# SparkFun-Blynk-Board-ESP8266.net
KiCad netlist of a schematic drawn in EAGLE
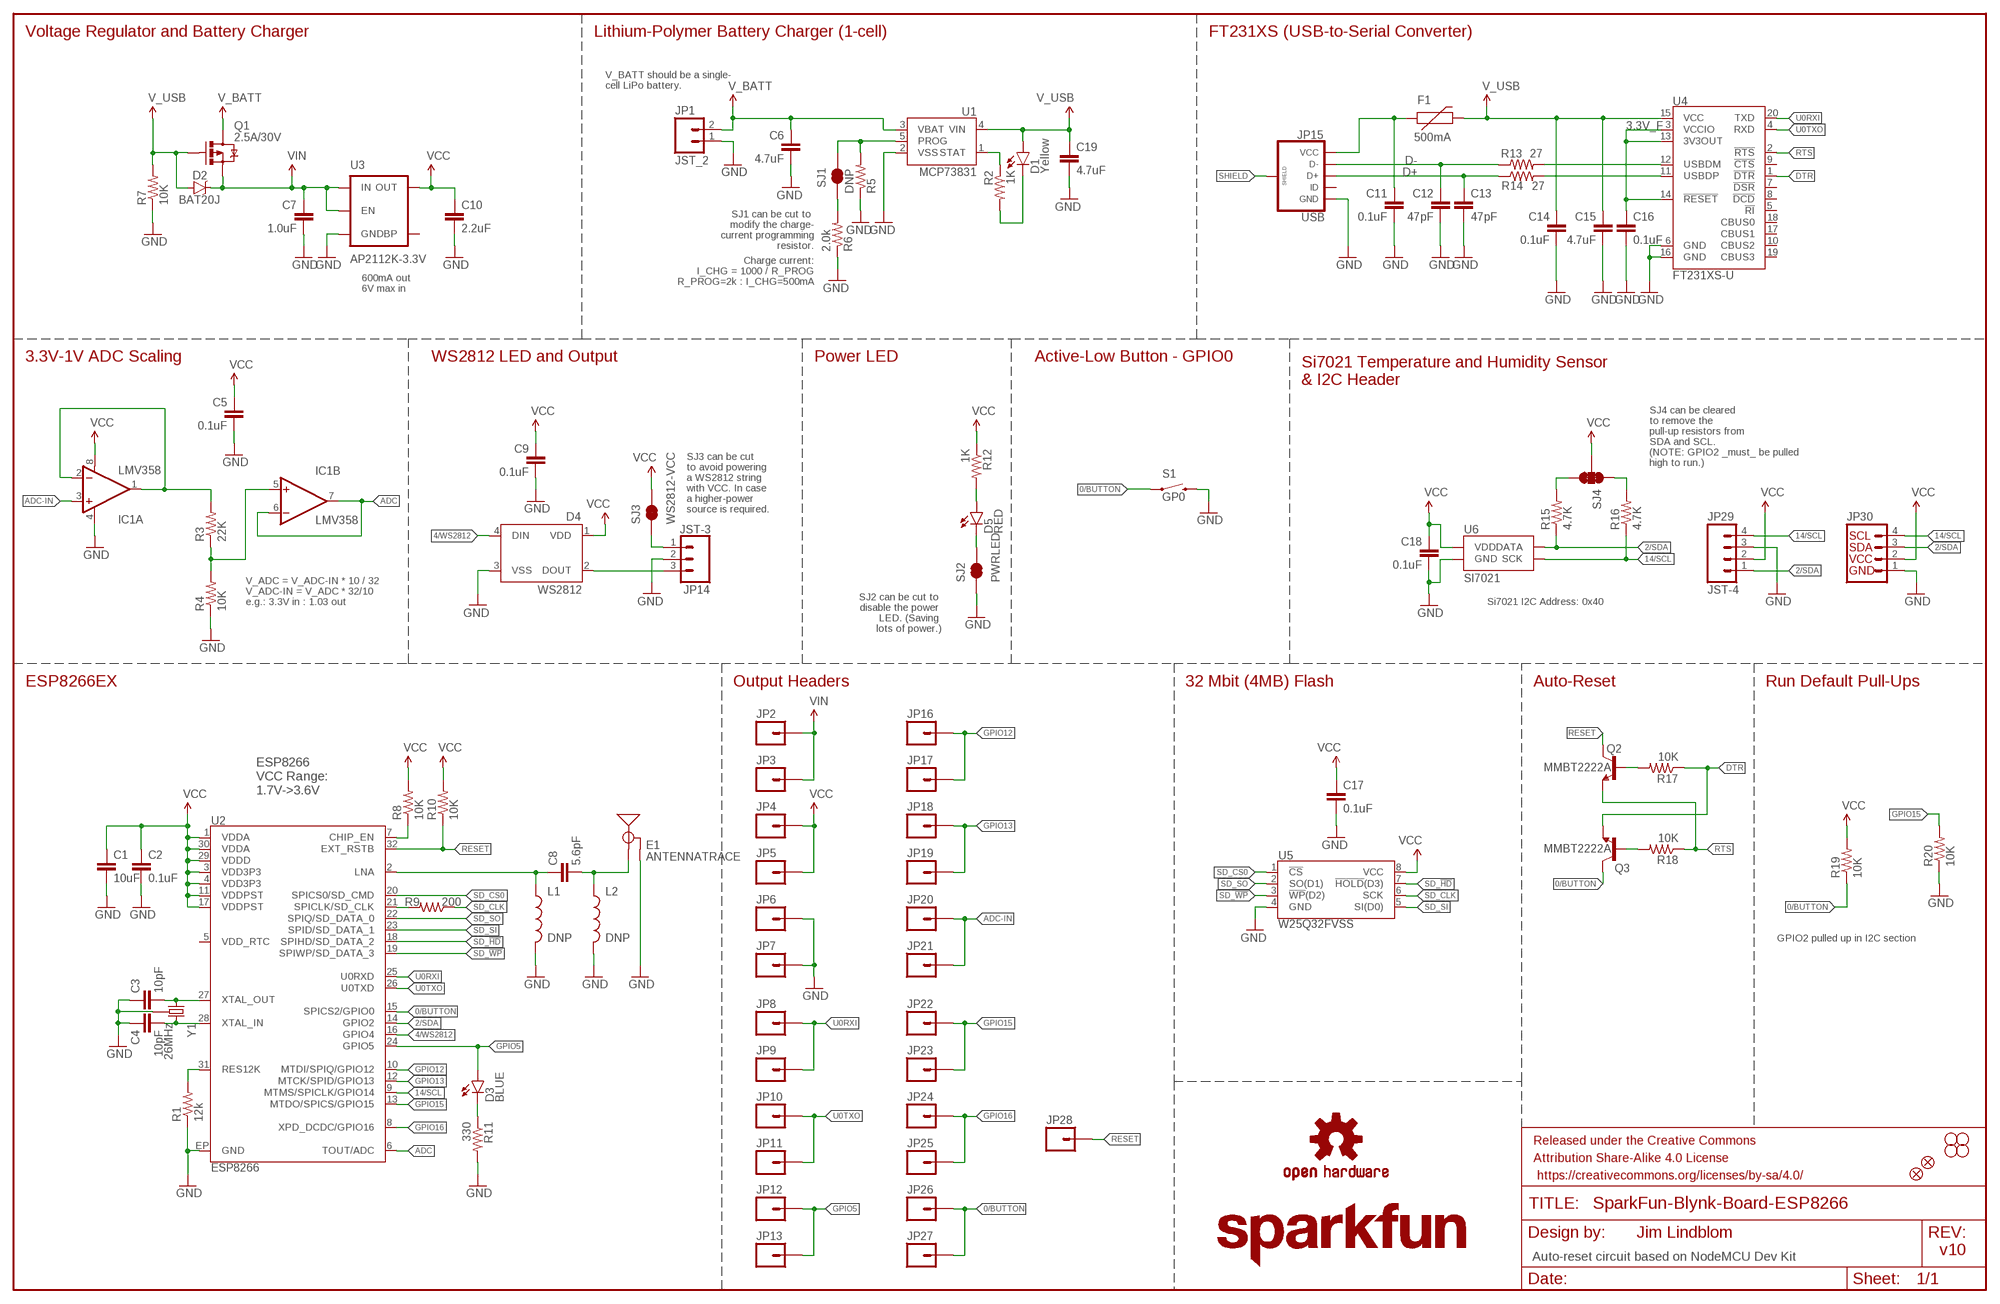
[diagram p0: schematic, sheet 1]

(export (version "E")
  (design (tool "Eeschema 10.0.6"))
  (components
    (comp (ref "C1")
      (value "10uF")
      (footprint "eagle-import:0603-CAP")
      (libsource (lib "eagle-import") (part "10UF-6.3V-20%(0603)"))
    )
    (comp (ref "C2")
      (value "0.1uF")
      (footprint "eagle-import:0603-CAP")
      (libsource (lib "eagle-import") (part "0.1UF-25V(+80/-20%)(0603)"))
    )
    (comp (ref "C3")
      (value "10pF")
      (footprint "eagle-import:0603-CAP")
      (libsource (lib "eagle-import") (part "10PF-50V-5%(0603)"))
    )
    (comp (ref "C4")
      (value "10pF")
      (footprint "eagle-import:0603-CAP")
      (libsource (lib "eagle-import") (part "10PF-50V-5%(0603)"))
    )
    (comp (ref "C5")
      (value "0.1uF")
      (footprint "eagle-import:0603-CAP")
      (libsource (lib "eagle-import") (part "0.1UF-25V(+80/-20%)(0603)"))
    )
    (comp (ref "C6")
      (value "4.7uF")
      (footprint "eagle-import:0603-CAP")
      (libsource (lib "eagle-import") (part "4.7UF-6.3V-10%(0603)0603"))
    )
    (comp (ref "C7")
      (value "1.0uF")
      (footprint "eagle-import:0805-CAP")
      (libsource (lib "eagle-import") (part "1.0UF-25V-+80/-20(0805){dblquote}"))
    )
    (comp (ref "C8")
      (value "5.6pF")
      (footprint "eagle-import:0603-CAP")
      (libsource (lib "eagle-import") (part "CAP0603-CAP"))
    )
    (comp (ref "C9")
      (value "0.1uF")
      (footprint "eagle-import:0603-CAP")
      (libsource (lib "eagle-import") (part "0.1UF-25V(+80/-20%)(0603)"))
    )
    (comp (ref "C10")
      (value "2.2uF")
      (footprint "eagle-import:0603-CAP")
      (libsource (lib "eagle-import") (part "2.2UF-10V-20%(0603)"))
    )
    (comp (ref "C11")
      (value "0.1uF")
      (footprint "eagle-import:0603-CAP")
      (libsource (lib "eagle-import") (part "0.1UF-25V(+80/-20%)(0603)"))
    )
    (comp (ref "C12")
      (value "47pF")
      (footprint "eagle-import:0603-CAP")
      (libsource (lib "eagle-import") (part "47PF-50V-5%(0603)"))
    )
    (comp (ref "C13")
      (value "47pF")
      (footprint "eagle-import:0603-CAP")
      (libsource (lib "eagle-import") (part "47PF-50V-5%(0603)"))
    )
    (comp (ref "C14")
      (value "0.1uF")
      (footprint "eagle-import:0603-CAP")
      (libsource (lib "eagle-import") (part "0.1UF-25V(+80/-20%)(0603)"))
    )
    (comp (ref "C15")
      (value "4.7uF")
      (footprint "eagle-import:0603-CAP")
      (libsource (lib "eagle-import") (part "4.7UF-6.3V-10%(0603)0603"))
    )
    (comp (ref "C16")
      (value "0.1uF")
      (footprint "eagle-import:0603-CAP")
      (libsource (lib "eagle-import") (part "0.1UF-25V(+80/-20%)(0603)"))
    )
    (comp (ref "C17")
      (value "0.1uF")
      (footprint "eagle-import:0603-CAP")
      (libsource (lib "eagle-import") (part "0.1UF-25V(+80/-20%)(0603)"))
    )
    (comp (ref "C18")
      (value "0.1uF")
      (footprint "eagle-import:0603-CAP")
      (libsource (lib "eagle-import") (part "0.1UF-25V(+80/-20%)(0603)"))
    )
    (comp (ref "C19")
      (value "4.7uF")
      (footprint "eagle-import:0603-CAP")
      (libsource (lib "eagle-import") (part "4.7UF-6.3V-10%(0603)0603"))
    )
    (comp (ref "D1")
      (value "Yellow")
      (footprint "eagle-import:LED-0603")
      (libsource (lib "eagle-import") (part "LED-YELLOW0603"))
    )
    (comp (ref "D2")
      (value "BAT20J")
      (footprint "eagle-import:SOD-323")
      (libsource (lib "eagle-import") (part "DIODE-SCHOTTKY-BAT20J"))
    )
    (comp (ref "D3")
      (value "BLUE")
      (footprint "eagle-import:LED-0603")
      (libsource (lib "eagle-import") (part "LED-BLUE0603"))
    )
    (comp (ref "D4")
      (value "WS2812")
      (footprint "eagle-import:WS2812B")
      (libsource (lib "eagle-import") (part "WS2812B"))
    )
    (comp (ref "D5")
      (value "RED")
      (footprint "eagle-import:LED-0603")
      (libsource (lib "eagle-import") (part "LED-RED0603"))
    )
    (comp (ref "E1")
      (value "ANTENNATRACE")
      (footprint "eagle-import:TRACE_ANTENNA_2.4GHZ_25.7MM")
      (libsource (lib "eagle-import") (part "ANTENNATRACE"))
    )
    (comp (ref "F1")
      (value "500mA")
      (footprint "eagle-import:PTC-1206")
      (libsource (lib "eagle-import") (part "PTCSMD"))
    )
    (comp (ref "FID1")
      (value "FIDUCIAL1X2")
      (footprint "eagle-import:FIDUCIAL-1X2")
      (libsource (lib "eagle-import") (part "FIDUCIAL1X2"))
    )
    (comp (ref "FID2")
      (value "FIDUCIAL1X2")
      (footprint "eagle-import:FIDUCIAL-1X2")
      (libsource (lib "eagle-import") (part "FIDUCIAL1X2"))
    )
    (comp (ref "FRAME1")
      (value "FRAME-LEDGER")
      (footprint "eagle-import:CREATIVE_COMMONS")
      (libsource (lib "eagle-import") (part "FRAME-LEDGER"))
    )
    (comp (ref "IC1")
      (value "LMV358")
      (footprint "eagle-import:SO08")
      (fields (field (name "PROD_ID") "IC-09657"))
      (libsource (lib "eagle-import") (part "OPAMP-DUALU"))
    )
    (comp (ref "JP1")
      (value "JST_2")
      (footprint "eagle-import:JST-2-PTH")
      (libsource (lib "eagle-import") (part "M02JST-PTH-2"))
    )
    (comp (ref "JP2")
      (value "DNP")
      (footprint "eagle-import:1X01_ALLIGATOR_3MM_HALF")
      (libsource (lib "eagle-import") (part "M01ALLIGATOR_HALF"))
    )
    (comp (ref "JP3")
      (value "DNP")
      (footprint "eagle-import:1X01_NO_SILK")
      (libsource (lib "eagle-import") (part "M01PTH_NO_SILK_YES_STOP"))
    )
    (comp (ref "JP4")
      (value "DNP")
      (footprint "eagle-import:1X01_ALLIGATOR_3MM_HALF")
      (libsource (lib "eagle-import") (part "M01ALLIGATOR_HALF"))
    )
    (comp (ref "JP5")
      (value "DNP")
      (footprint "eagle-import:1X01_NO_SILK")
      (libsource (lib "eagle-import") (part "M01PTH_NO_SILK_YES_STOP"))
    )
    (comp (ref "JP6")
      (value "DNP")
      (footprint "eagle-import:1X01_ALLIGATOR_3MM_HALF")
      (libsource (lib "eagle-import") (part "M01ALLIGATOR_HALF"))
    )
    (comp (ref "JP7")
      (value "DNP")
      (footprint "eagle-import:1X01_NO_SILK")
      (libsource (lib "eagle-import") (part "M01PTH_NO_SILK_YES_STOP"))
    )
    (comp (ref "JP8")
      (value "DNP")
      (footprint "eagle-import:1X01_ALLIGATOR_3MM_HALF")
      (libsource (lib "eagle-import") (part "M01ALLIGATOR_HALF"))
    )
    (comp (ref "JP9")
      (value "DNP")
      (footprint "eagle-import:1X01_NO_SILK")
      (libsource (lib "eagle-import") (part "M01PTH_NO_SILK_YES_STOP"))
    )
    (comp (ref "JP10")
      (value "DNP")
      (footprint "eagle-import:1X01_ALLIGATOR_3MM_HALF")
      (libsource (lib "eagle-import") (part "M01ALLIGATOR_HALF"))
    )
    (comp (ref "JP11")
      (value "DNP")
      (footprint "eagle-import:1X01_NO_SILK")
      (libsource (lib "eagle-import") (part "M01PTH_NO_SILK_YES_STOP"))
    )
    (comp (ref "JP12")
      (value "DNP")
      (footprint "eagle-import:1X01_ALLIGATOR_3MM_HALF")
      (libsource (lib "eagle-import") (part "M01ALLIGATOR_HALF"))
    )
    (comp (ref "JP13")
      (value "DNP")
      (footprint "eagle-import:1X01_NO_SILK")
      (libsource (lib "eagle-import") (part "M01PTH_NO_SILK_YES_STOP"))
    )
    (comp (ref "JP14")
      (value "JST-3")
      (footprint "eagle-import:JST-3-PTH-VERT")
      (libsource (lib "eagle-import") (part "M03JST-PTH-VERT"))
    )
    (comp (ref "JP15")
      (value "USB")
      (footprint "eagle-import:USB-B-MICRO-SMD_V03")
      (libsource (lib "eagle-import") (part "USB_MICROB_PLUGCONN-11752"))
    )
    (comp (ref "JP16")
      (value "DNP")
      (footprint "eagle-import:1X01_ALLIGATOR_3MM_HALF")
      (libsource (lib "eagle-import") (part "M01ALLIGATOR_HALF"))
    )
    (comp (ref "JP17")
      (value "DNP")
      (footprint "eagle-import:1X01_NO_SILK")
      (libsource (lib "eagle-import") (part "M01PTH_NO_SILK_YES_STOP"))
    )
    (comp (ref "JP18")
      (value "DNP")
      (footprint "eagle-import:1X01_ALLIGATOR_3MM_HALF")
      (libsource (lib "eagle-import") (part "M01ALLIGATOR_HALF"))
    )
    (comp (ref "JP19")
      (value "DNP")
      (footprint "eagle-import:1X01_NO_SILK")
      (libsource (lib "eagle-import") (part "M01PTH_NO_SILK_YES_STOP"))
    )
    (comp (ref "JP20")
      (value "DNP")
      (footprint "eagle-import:1X01_ALLIGATOR_3MM_HALF")
      (libsource (lib "eagle-import") (part "M01ALLIGATOR_HALF"))
    )
    (comp (ref "JP21")
      (value "DNP")
      (footprint "eagle-import:1X01_NO_SILK")
      (libsource (lib "eagle-import") (part "M01PTH_NO_SILK_YES_STOP"))
    )
    (comp (ref "JP22")
      (value "DNP")
      (footprint "eagle-import:1X01_ALLIGATOR_3MM_HALF")
      (libsource (lib "eagle-import") (part "M01ALLIGATOR_HALF"))
    )
    (comp (ref "JP23")
      (value "DNP")
      (footprint "eagle-import:1X01_NO_SILK")
      (libsource (lib "eagle-import") (part "M01PTH_NO_SILK_YES_STOP"))
    )
    (comp (ref "JP24")
      (value "DNP")
      (footprint "eagle-import:1X01_ALLIGATOR_3MM_HALF")
      (libsource (lib "eagle-import") (part "M01ALLIGATOR_HALF"))
    )
    (comp (ref "JP25")
      (value "DNP")
      (footprint "eagle-import:1X01_NO_SILK")
      (libsource (lib "eagle-import") (part "M01PTH_NO_SILK_YES_STOP"))
    )
    (comp (ref "JP26")
      (value "DNP")
      (footprint "eagle-import:1X01_ALLIGATOR_3MM_HALF")
      (libsource (lib "eagle-import") (part "M01ALLIGATOR_HALF"))
    )
    (comp (ref "JP27")
      (value "DNP")
      (footprint "eagle-import:1X01_NO_SILK")
      (libsource (lib "eagle-import") (part "M01PTH_NO_SILK_YES_STOP"))
    )
    (comp (ref "JP28")
      (value "DNP")
      (footprint "eagle-import:1X01_NO_SILK")
      (libsource (lib "eagle-import") (part "M01PTH_NO_SILK_YES_STOP"))
    )
    (comp (ref "JP29")
      (value "JST-4")
      (footprint "eagle-import:JST-4-PTH-VERT")
      (libsource (lib "eagle-import") (part "M04JST-PTH-VERT"))
    )
    (comp (ref "JP30")
      (value "DNP")
      (footprint "eagle-import:1X04_NO_SILK")
      (libsource (lib "eagle-import") (part "I2C_STANDARD_NO_SILK"))
    )
    (comp (ref "L1")
      (value "DNP")
      (footprint "eagle-import:0603")
      (libsource (lib "eagle-import") (part "INDUCTOR0603"))
    )
    (comp (ref "L2")
      (value "DNP")
      (footprint "eagle-import:0603")
      (libsource (lib "eagle-import") (part "INDUCTOR0603"))
    )
    (comp (ref "LOGO1")
      (value "SFE_LOGO_NAME.2_INCH")
      (footprint "eagle-import:SFE_LOGO_NAME_.2")
      (libsource (lib "eagle-import") (part "SFE_LOGO_NAME.2_INCH"))
    )
    (comp (ref "LOGO2")
      (value "OSHW-LOGOS")
      (footprint "eagle-import:OSHW-LOGO-S")
      (libsource (lib "eagle-import") (part "OSHW-LOGOS"))
    )
    (comp (ref "LOGO3")
      (value "SFE_LOGO_NAME.3_INCH")
      (footprint "eagle-import:SFE_LOGO_NAME_.3")
      (libsource (lib "eagle-import") (part "SFE_LOGO_NAME.3_INCH"))
    )
    (comp (ref "Q1")
      (value "2.5A/30V")
      (footprint "eagle-import:SOT23-3")
      (libsource (lib "eagle-import") (part "MOSFET-PCHANNELDMG2307L"))
    )
    (comp (ref "Q2")
      (value "MMBT2222A")
      (footprint "eagle-import:SOT23-3@1")
      (libsource (lib "eagle-import") (part "TRANSISTOR_NPNMMBT2222A"))
    )
    (comp (ref "Q3")
      (value "MMBT2222A")
      (footprint "eagle-import:SOT23-3@1")
      (libsource (lib "eagle-import") (part "TRANSISTOR_NPNMMBT2222A"))
    )
    (comp (ref "R1")
      (value "12k")
      (footprint "eagle-import:0603-RES")
      (libsource (lib "eagle-import") (part "12KOHM-1/10W-1%(0603)"))
    )
    (comp (ref "R2")
      (value "1K")
      (footprint "eagle-import:0603-RES")
      (libsource (lib "eagle-import") (part "1KOHM-1/10W-1%(0603)"))
    )
    (comp (ref "R3")
      (value "22K")
      (footprint "eagle-import:0603-RES")
      (libsource (lib "eagle-import") (part "22KOHM1/10W1%(0603)"))
    )
    (comp (ref "R4")
      (value "10K")
      (footprint "eagle-import:0603-RES")
      (libsource (lib "eagle-import") (part "10KOHM-1/10W-1%(0603)0603"))
    )
    (comp (ref "R5")
      (value "DNP")
      (footprint "eagle-import:1_6W-RES")
      (libsource (lib "eagle-import") (part "RESISTORPTH-1/6W"))
    )
    (comp (ref "R6")
      (value "2.0k")
      (footprint "eagle-import:0603-RES")
      (libsource (lib "eagle-import") (part "2.0KOHM1/10W5%(0603)"))
    )
    (comp (ref "R7")
      (value "10K")
      (footprint "eagle-import:0603-RES@1")
      (libsource (lib "eagle-import") (part "10KOHM1/10W1%(0603)0603"))
    )
    (comp (ref "R8")
      (value "10K")
      (footprint "eagle-import:0603-RES@1")
      (libsource (lib "eagle-import") (part "10KOHM1/10W1%(0603)0603"))
    )
    (comp (ref "R9")
      (value "200")
      (footprint "eagle-import:0603-RES")
      (libsource (lib "eagle-import") (part "200OHM1/10W1%(0603)"))
    )
    (comp (ref "R10")
      (value "10K")
      (footprint "eagle-import:0603-RES@1")
      (libsource (lib "eagle-import") (part "10KOHM1/10W1%(0603)0603"))
    )
    (comp (ref "R11")
      (value "330")
      (footprint "eagle-import:0603-RES")
      (libsource (lib "eagle-import") (part "330OHM1/10W1%(0603)"))
    )
    (comp (ref "R12")
      (value "1K")
      (footprint "eagle-import:0603-RES")
      (libsource (lib "eagle-import") (part "1KOHM-1/10W-1%(0603)"))
    )
    (comp (ref "R13")
      (value "27")
      (footprint "eagle-import:0603-RES")
      (libsource (lib "eagle-import") (part "27OHM1/10W1%(0603)0603-RES"))
    )
    (comp (ref "R14")
      (value "27")
      (footprint "eagle-import:0603-RES")
      (libsource (lib "eagle-import") (part "27OHM1/10W1%(0603)0603-RES"))
    )
    (comp (ref "R15")
      (value "4.7K")
      (footprint "eagle-import:0603-RES")
      (libsource (lib "eagle-import") (part "4.7KOHM-1/10W-1%(0603)"))
    )
    (comp (ref "R16")
      (value "4.7K")
      (footprint "eagle-import:0603-RES")
      (libsource (lib "eagle-import") (part "4.7KOHM-1/10W-1%(0603)"))
    )
    (comp (ref "R17")
      (value "10K")
      (footprint "eagle-import:0603-RES@1")
      (libsource (lib "eagle-import") (part "10KOHM1/10W1%(0603)0603"))
    )
    (comp (ref "R18")
      (value "10K")
      (footprint "eagle-import:0603-RES@1")
      (libsource (lib "eagle-import") (part "10KOHM1/10W1%(0603)0603"))
    )
    (comp (ref "R19")
      (value "10K")
      (footprint "eagle-import:0603-RES@1")
      (libsource (lib "eagle-import") (part "10KOHM1/10W1%(0603)0603"))
    )
    (comp (ref "R20")
      (value "10K")
      (footprint "eagle-import:0603-RES@1")
      (libsource (lib "eagle-import") (part "10KOHM1/10W1%(0603)0603"))
    )
    (comp (ref "S1")
      (value "GP0")
      (footprint "eagle-import:TACTILE-SWITCH-SMD")
      (libsource (lib "eagle-import") (part "SWITCH-MOMENTARY-2SMD-REDUNDANT"))
    )
    (comp (ref "SJ1")
      (value "DNP")
      (footprint "eagle-import:PAD-JUMPER-2-NC_BY_TRACE_YES_SILK")
      (libsource (lib "eagle-import") (part "JUMPER-PAD-2-NC_BY_TRACE"))
    )
    (comp (ref "SJ2")
      (value "PWRLED")
      (footprint "eagle-import:PAD-JUMPER-2-NC_BY_TRACE_YES_SILK")
      (libsource (lib "eagle-import") (part "JUMPER-PAD-2-NC_BY_TRACE"))
    )
    (comp (ref "SJ3")
      (value "WS2812-VCC")
      (footprint "eagle-import:PAD-JUMPER-2-NC_BY_TRACE_YES_SILK")
      (libsource (lib "eagle-import") (part "JUMPER-PAD-2-NC_BY_TRACE"))
    )
    (comp (ref "SJ4")
      (value "DNP")
      (footprint "eagle-import:PAD-JUMPER-3-3OF3_NC_BY_TRACE_YES_SILK_FULL_BOX")
      (libsource (lib "eagle-import") (part "JUMPER-PAD-3-NC_BY_TRACE"))
    )
    (comp (ref "STANDOFF1")
      (value "STAND-OFF")
      (footprint "eagle-import:STAND-OFF")
      (libsource (lib "eagle-import") (part "STAND-OFF"))
    )
    (comp (ref "STANDOFF2")
      (value "STAND-OFF")
      (footprint "eagle-import:STAND-OFF")
      (libsource (lib "eagle-import") (part "STAND-OFF"))
    )
    (comp (ref "STANDOFF3")
      (value "STAND-OFF")
      (footprint "eagle-import:STAND-OFF")
      (libsource (lib "eagle-import") (part "STAND-OFF"))
    )
    (comp (ref "STANDOFF4")
      (value "STAND-OFF")
      (footprint "eagle-import:STAND-OFF")
      (libsource (lib "eagle-import") (part "STAND-OFF"))
    )
    (comp (ref "U1")
      (value "MCP73831")
      (footprint "eagle-import:SOT23-5")
      (libsource (lib "eagle-import") (part "MCP73831"))
    )
    (comp (ref "U2")
      (value "ESP8266")
      (footprint "eagle-import:QFN32")
      (fields (field (name "PROD_ID") "IC-12452"))
      (libsource (lib "eagle-import") (part "ESP8266"))
    )
    (comp (ref "U3")
      (value "AP2112K-3.3V")
      (footprint "eagle-import:SOT23-5")
      (libsource (lib "eagle-import") (part "V_REG_LDOSMD"))
    )
    (comp (ref "U4")
      (value "FT231XS-U")
      (footprint "eagle-import:SSOP20_L")
      (libsource (lib "eagle-import") (part "FT231XS"))
    )
    (comp (ref "U5")
      (value "W25Q32FVSS")
      (footprint "eagle-import:SOIC-8")
      (fields (field (name "PROD_ID") "IC-13229"))
      (libsource (lib "eagle-import") (part "W25Q32FVSS"))
    )
    (comp (ref "U6")
      (value "SI7021")
      (footprint "eagle-import:SI7021")
      (libsource (lib "eagle-import") (part "SI7021"))
    )
    (comp (ref "Y1")
      (value "26MHz")
      (footprint "eagle-import:CRYSTAL-SMD-3.2X2.5")
      (libsource (lib "eagle-import") (part "CRYSTAL-GROUNDED3.2X2.5"))
    )
  )
  (nets
    (net (code "1") (name "/3.3V_F") (class "Default")
      (node (ref "C16") (pin "1") (pinfunction "1_1") (pintype "passive"))
      (node (ref "U4") (pin "13") (pinfunction "3V3OUT_13") (pintype "bidirectional"))
      (node (ref "U4") (pin "14") (pinfunction "~{RESET}_14") (pintype "bidirectional"))
      (node (ref "U4") (pin "3") (pinfunction "VCCIO_3") (pintype "bidirectional"))
    )
    (net (code "2") (name "/D+") (class "Default")
      (node (ref "C13") (pin "1") (pinfunction "1_1") (pintype "passive"))
      (node (ref "JP15") (pin "D+") (pinfunction "D+_D+") (pintype "bidirectional"))
      (node (ref "R14") (pin "1") (pinfunction "1_1") (pintype "passive"))
    )
    (net (code "3") (name "/D-") (class "Default")
      (node (ref "C12") (pin "1") (pinfunction "1_1") (pintype "passive"))
      (node (ref "JP15") (pin "D-") (pinfunction "D-_D-") (pintype "bidirectional"))
      (node (ref "R13") (pin "1") (pinfunction "1_1") (pintype "passive"))
    )
    (net (code "4") (name "/SD_~{HD}") (class "Default")
      (node (ref "U2") (pin "18") (pinfunction "SPIHD/SD_DATA_2_18") (pintype "bidirectional"))
      (node (ref "U5") (pin "7") (pinfunction "~{HOLD}(D3)_7") (pintype "bidirectional"))
    )
    (net (code "5") (name "/SD_~{WP}") (class "Default")
      (node (ref "U2") (pin "19") (pinfunction "SPIWP/SD_DATA_3_19") (pintype "bidirectional"))
      (node (ref "U5") (pin "3") (pinfunction "~{WP}(D2)_3") (pintype "bidirectional"))
    )
    (net (code "6") (name "0{slash}BUTTON") (class "Default")
      (node (ref "JP26") (pin "1@2") (pinfunction "1_1@2") (pintype "passive"))
      (node (ref "JP27") (pin "1") (pinfunction "1_1") (pintype "passive"))
      (node (ref "Q3") (pin "3") (pinfunction "C_3") (pintype "passive"))
      (node (ref "R19") (pin "1") (pinfunction "1_1") (pintype "passive"))
      (node (ref "S1") (pin "1") (pinfunction "1_1") (pintype "passive"))
      (node (ref "S1") (pin "2") (pinfunction "1_2") (pintype "passive"))
      (node (ref "U2") (pin "15") (pinfunction "SPICS2/GPIO0_15") (pintype "bidirectional"))
    )
    (net (code "7") (name "2{slash}SDA") (class "Default")
      (node (ref "JP29") (pin "1") (pinfunction "1_1") (pintype "passive"))
      (node (ref "JP30") (pin "3") (pinfunction "3_3") (pintype "passive"))
      (node (ref "R15") (pin "1") (pinfunction "1_1") (pintype "passive"))
      (node (ref "U2") (pin "14") (pinfunction "GPIO2_14") (pintype "bidirectional"))
      (node (ref "U6") (pin "DATA") (pinfunction "DATA_DATA") (pintype "bidirectional"))
    )
    (net (code "8") (name "4{slash}WS2812") (class "Default")
      (node (ref "D4") (pin "4") (pinfunction "DIN_4") (pintype "input"))
      (node (ref "U2") (pin "16") (pinfunction "GPIO4_16") (pintype "bidirectional"))
    )
    (net (code "9") (name "14{slash}SCL") (class "Default")
      (node (ref "JP29") (pin "4") (pinfunction "4_4") (pintype "passive"))
      (node (ref "JP30") (pin "4") (pinfunction "4_4") (pintype "passive"))
      (node (ref "R16") (pin "1") (pinfunction "1_1") (pintype "passive"))
      (node (ref "U2") (pin "9") (pinfunction "MTMS/SPICLK/GPIO14_9") (pintype "bidirectional"))
      (node (ref "U6") (pin "SCK") (pinfunction "SCK_SCK") (pintype "input"))
    )
    (net (code "10") (name "ADC") (class "Default")
      (node (ref "IC1") (pin "6") (pinfunction "-IN_6") (pintype "input"))
      (node (ref "IC1") (pin "7") (pinfunction "OUT_7") (pintype "output"))
      (node (ref "U2") (pin "6") (pinfunction "TOUT/ADC_6") (pintype "bidirectional"))
    )
    (net (code "11") (name "ADC-IN") (class "Default")
      (node (ref "IC1") (pin "3") (pinfunction "+IN_3") (pintype "input"))
      (node (ref "JP20") (pin "1@2") (pinfunction "1_1@2") (pintype "passive"))
      (node (ref "JP21") (pin "1") (pinfunction "1_1") (pintype "passive"))
    )
    (net (code "12") (name "DTR") (class "Default")
      (node (ref "Q3") (pin "2") (pinfunction "E_2") (pintype "passive"))
      (node (ref "R17") (pin "1") (pinfunction "1_1") (pintype "passive"))
      (node (ref "U4") (pin "1") (pinfunction "~{DTR}_1") (pintype "bidirectional"))
    )
    (net (code "13") (name "GND") (class "Default")
      (node (ref "C1") (pin "2") (pinfunction "2_2") (pintype "passive"))
      (node (ref "C10") (pin "2") (pinfunction "2_2") (pintype "passive"))
      (node (ref "C11") (pin "2") (pinfunction "2_2") (pintype "passive"))
      (node (ref "C12") (pin "2") (pinfunction "2_2") (pintype "passive"))
      (node (ref "C13") (pin "2") (pinfunction "2_2") (pintype "passive"))
      (node (ref "C14") (pin "2") (pinfunction "2_2") (pintype "passive"))
      (node (ref "C15") (pin "2") (pinfunction "2_2") (pintype "passive"))
      (node (ref "C16") (pin "2") (pinfunction "2_2") (pintype "passive"))
      (node (ref "C17") (pin "2") (pinfunction "2_2") (pintype "passive"))
      (node (ref "C18") (pin "2") (pinfunction "2_2") (pintype "passive"))
      (node (ref "C19") (pin "2") (pinfunction "2_2") (pintype "passive"))
      (node (ref "C2") (pin "2") (pinfunction "2_2") (pintype "passive"))
      (node (ref "C3") (pin "1") (pinfunction "1_1") (pintype "passive"))
      (node (ref "C4") (pin "1") (pinfunction "1_1") (pintype "passive"))
      (node (ref "C5") (pin "2") (pinfunction "2_2") (pintype "passive"))
      (node (ref "C6") (pin "2") (pinfunction "2_2") (pintype "passive"))
      (node (ref "C7") (pin "2") (pinfunction "2_2") (pintype "passive"))
      (node (ref "C9") (pin "2") (pinfunction "2_2") (pintype "passive"))
      (node (ref "D4") (pin "3") (pinfunction "VSS_3") (pintype "power_in"))
      (node (ref "E1") (pin "GND") (pinfunction "GND_GND") (pintype "bidirectional"))
      (node (ref "E1") (pin "GND2") (pinfunction "GND_GND2") (pintype "bidirectional"))
      (node (ref "IC1") (pin "4") (pinfunction "V-_4") (pintype "power_in"))
      (node (ref "JP1") (pin "1") (pinfunction "1_1") (pintype "passive"))
      (node (ref "JP14") (pin "2") (pinfunction "2_2") (pintype "passive"))
      (node (ref "JP15") (pin "GND") (pinfunction "GND_GND") (pintype "bidirectional"))
      (node (ref "JP29") (pin "3") (pinfunction "3_3") (pintype "passive"))
      (node (ref "JP30") (pin "1") (pinfunction "1_1") (pintype "passive"))
      (node (ref "JP6") (pin "1@2") (pinfunction "1_1@2") (pintype "passive"))
      (node (ref "JP7") (pin "1") (pinfunction "1_1") (pintype "passive"))
      (node (ref "L1") (pin "2") (pinfunction "2_2") (pintype "passive"))
      (node (ref "L2") (pin "2") (pinfunction "2_2") (pintype "passive"))
      (node (ref "R1") (pin "1") (pinfunction "1_1") (pintype "passive"))
      (node (ref "R11") (pin "2") (pinfunction "2_2") (pintype "passive"))
      (node (ref "R20") (pin "1") (pinfunction "1_1") (pintype "passive"))
      (node (ref "R4") (pin "1") (pinfunction "1_1") (pintype "passive"))
      (node (ref "R5") (pin "1") (pinfunction "1_1") (pintype "passive"))
      (node (ref "R6") (pin "1") (pinfunction "1_1") (pintype "passive"))
      (node (ref "R7") (pin "1") (pinfunction "1_1") (pintype "passive"))
      (node (ref "S1") (pin "3") (pinfunction "2_3") (pintype "passive"))
      (node (ref "S1") (pin "4") (pinfunction "2_4") (pintype "passive"))
      (node (ref "SJ2") (pin "1") (pinfunction "1_1") (pintype "passive"))
      (node (ref "U1") (pin "2") (pinfunction "VSS_2") (pintype "power_in"))
      (node (ref "U2") (pin "EP") (pinfunction "GND_EP") (pintype "bidirectional"))
      (node (ref "U3") (pin "2") (pinfunction "GND_2") (pintype "input"))
      (node (ref "U4") (pin "16") (pinfunction "GND_16") (pintype "bidirectional"))
      (node (ref "U4") (pin "6") (pinfunction "GND_6") (pintype "bidirectional"))
      (node (ref "U5") (pin "4") (pinfunction "GND_4") (pintype "bidirectional"))
      (node (ref "U6") (pin "GND") (pinfunction "GND_GND") (pintype "power_in"))
      (node (ref "Y1") (pin "2") (pinfunction "GND_2") (pintype "passive"))
      (node (ref "Y1") (pin "4") (pinfunction "GND_4") (pintype "passive"))
    )
    (net (code "14") (name "GPIO5") (class "Default")
      (node (ref "D3") (pin "A") (pinfunction "A_A") (pintype "passive"))
      (node (ref "JP12") (pin "1@2") (pinfunction "1_1@2") (pintype "passive"))
      (node (ref "JP13") (pin "1") (pinfunction "1_1") (pintype "passive"))
      (node (ref "U2") (pin "24") (pinfunction "GPIO5_24") (pintype "bidirectional"))
    )
    (net (code "15") (name "GPIO12") (class "Default")
      (node (ref "JP16") (pin "1@2") (pinfunction "1_1@2") (pintype "passive"))
      (node (ref "JP17") (pin "1") (pinfunction "1_1") (pintype "passive"))
      (node (ref "U2") (pin "10") (pinfunction "MTDI/SPIQ/GPIO12_10") (pintype "bidirectional"))
    )
    (net (code "16") (name "GPIO13") (class "Default")
      (node (ref "JP18") (pin "1@2") (pinfunction "1_1@2") (pintype "passive"))
      (node (ref "JP19") (pin "1") (pinfunction "1_1") (pintype "passive"))
      (node (ref "U2") (pin "12") (pinfunction "MTCK/SPID/GPIO13_12") (pintype "bidirectional"))
    )
    (net (code "17") (name "GPIO15") (class "Default")
      (node (ref "JP22") (pin "1@2") (pinfunction "1_1@2") (pintype "passive"))
      (node (ref "JP23") (pin "1") (pinfunction "1_1") (pintype "passive"))
      (node (ref "R20") (pin "2") (pinfunction "2_2") (pintype "passive"))
      (node (ref "U2") (pin "13") (pinfunction "MTDO/SPICS/GPIO15_13") (pintype "bidirectional"))
    )
    (net (code "18") (name "GPIO16") (class "Default")
      (node (ref "JP24") (pin "1@2") (pinfunction "1_1@2") (pintype "passive"))
      (node (ref "JP25") (pin "1") (pinfunction "1_1") (pintype "passive"))
      (node (ref "U2") (pin "8") (pinfunction "XPD_DCDC/GPIO16_8") (pintype "bidirectional"))
    )
    (net (code "19") (name "Net-(D1-PadC)") (class "Default")
      (node (ref "D1") (pin "C") (pinfunction "C_C") (pintype "passive"))
      (node (ref "R2") (pin "2") (pinfunction "2_2") (pintype "passive"))
    )
    (net (code "20") (name "Net-(D3-PadC)") (class "Default")
      (node (ref "D3") (pin "C") (pinfunction "C_C") (pintype "passive"))
      (node (ref "R11") (pin "1") (pinfunction "1_1") (pintype "passive"))
    )
    (net (code "21") (name "Net-(D4-DOUT)") (class "Default")
      (node (ref "D4") (pin "2") (pinfunction "DOUT_2") (pintype "output"))
      (node (ref "JP14") (pin "3") (pinfunction "3_3") (pintype "passive"))
    )
    (net (code "22") (name "Net-(D5-PadA)") (class "Default")
      (node (ref "D5") (pin "A") (pinfunction "A_A") (pintype "passive"))
      (node (ref "R12") (pin "2") (pinfunction "2_2") (pintype "passive"))
    )
    (net (code "23") (name "Net-(D5-PadC)") (class "Default")
      (node (ref "D5") (pin "C") (pinfunction "C_C") (pintype "passive"))
      (node (ref "SJ2") (pin "2") (pinfunction "2_2") (pintype "passive"))
    )
    (net (code "24") (name "Net-(E1-SIGNAL)") (class "Default")
      (node (ref "C8") (pin "2") (pinfunction "2_2") (pintype "passive"))
      (node (ref "E1") (pin "ANT") (pinfunction "SIGNAL_ANT") (pintype "bidirectional"))
      (node (ref "L2") (pin "1") (pinfunction "1_1") (pintype "passive"))
    )
    (net (code "25") (name "Net-(IC1A--IN)") (class "Default")
      (node (ref "IC1") (pin "1") (pinfunction "OUT_1") (pintype "output"))
      (node (ref "IC1") (pin "2") (pinfunction "-IN_2") (pintype "input"))
      (node (ref "R3") (pin "2") (pinfunction "2_2") (pintype "passive"))
    )
    (net (code "26") (name "Net-(IC1B-+IN)") (class "Default")
      (node (ref "IC1") (pin "5") (pinfunction "+IN_5") (pintype "input"))
      (node (ref "R3") (pin "1") (pinfunction "1_1") (pintype "passive"))
      (node (ref "R4") (pin "2") (pinfunction "2_2") (pintype "passive"))
    )
    (net (code "27") (name "Net-(JP14-Pad1)") (class "Default")
      (node (ref "JP14") (pin "1") (pinfunction "1_1") (pintype "passive"))
      (node (ref "SJ3") (pin "1") (pinfunction "1_1") (pintype "passive"))
    )
    (net (code "28") (name "Net-(JP15-VCC)") (class "Default")
      (node (ref "C11") (pin "1") (pinfunction "1_1") (pintype "passive"))
      (node (ref "F1") (pin "1") (pinfunction "1_1") (pintype "bidirectional"))
      (node (ref "JP15") (pin "VBUS") (pinfunction "VCC_VBUS") (pintype "bidirectional"))
    )
    (net (code "29") (name "Net-(Q2-B)") (class "Default")
      (node (ref "Q2") (pin "1") (pinfunction "B_1") (pintype "passive"))
      (node (ref "R17") (pin "2") (pinfunction "2_2") (pintype "passive"))
    )
    (net (code "30") (name "Net-(Q3-B)") (class "Default")
      (node (ref "Q3") (pin "1") (pinfunction "B_1") (pintype "passive"))
      (node (ref "R18") (pin "2") (pinfunction "2_2") (pintype "passive"))
    )
    (net (code "31") (name "Net-(R6-Pad2)") (class "Default")
      (node (ref "R6") (pin "2") (pinfunction "2_2") (pintype "passive"))
      (node (ref "SJ1") (pin "1") (pinfunction "1_1") (pintype "passive"))
    )
    (net (code "32") (name "Net-(R15-Pad2)") (class "Default")
      (node (ref "R15") (pin "2") (pinfunction "2_2") (pintype "passive"))
      (node (ref "SJ4") (pin "3") (pinfunction "3_3") (pintype "passive"))
    )
    (net (code "33") (name "Net-(R16-Pad2)") (class "Default")
      (node (ref "R16") (pin "2") (pinfunction "2_2") (pintype "passive"))
      (node (ref "SJ4") (pin "1") (pinfunction "1_1") (pintype "passive"))
    )
    (net (code "34") (name "Net-(U1-PROG)") (class "Default")
      (node (ref "R5") (pin "2") (pinfunction "2_2") (pintype "passive"))
      (node (ref "SJ1") (pin "2") (pinfunction "2_2") (pintype "passive"))
      (node (ref "U1") (pin "5") (pinfunction "PROG_5") (pintype "input"))
    )
    (net (code "35") (name "Net-(U1-STAT)") (class "Default")
      (node (ref "R2") (pin "1") (pinfunction "1_1") (pintype "passive"))
      (node (ref "U1") (pin "1") (pinfunction "STAT_1") (pintype "output"))
    )
    (net (code "36") (name "Net-(U2-CHIP_EN)") (class "Default")
      (node (ref "R8") (pin "1") (pinfunction "1_1") (pintype "passive"))
      (node (ref "U2") (pin "7") (pinfunction "CHIP_EN_7") (pintype "bidirectional"))
    )
    (net (code "37") (name "Net-(U2-LNA)") (class "Default")
      (node (ref "C8") (pin "1") (pinfunction "1_1") (pintype "passive"))
      (node (ref "L1") (pin "1") (pinfunction "1_1") (pintype "passive"))
      (node (ref "U2") (pin "2") (pinfunction "LNA_2") (pintype "bidirectional"))
    )
    (net (code "38") (name "Net-(U2-RES12K)") (class "Default")
      (node (ref "R1") (pin "2") (pinfunction "2_2") (pintype "passive"))
      (node (ref "U2") (pin "31") (pinfunction "RES12K_31") (pintype "bidirectional"))
    )
    (net (code "39") (name "Net-(U2-SPICLK{slash}SD_CLK)") (class "Default")
      (node (ref "R9") (pin "2") (pinfunction "2_2") (pintype "passive"))
      (node (ref "U2") (pin "21") (pinfunction "SPICLK/SD_CLK_21") (pintype "bidirectional"))
    )
    (net (code "40") (name "Net-(U2-XTAL_IN)") (class "Default")
      (node (ref "C4") (pin "2") (pinfunction "2_2") (pintype "passive"))
      (node (ref "U2") (pin "28") (pinfunction "XTAL_IN_28") (pintype "bidirectional"))
      (node (ref "Y1") (pin "3") (pinfunction "2_3") (pintype "passive"))
    )
    (net (code "41") (name "Net-(U2-XTAL_OUT)") (class "Default")
      (node (ref "C3") (pin "2") (pinfunction "2_2") (pintype "passive"))
      (node (ref "U2") (pin "27") (pinfunction "XTAL_OUT_27") (pintype "bidirectional"))
      (node (ref "Y1") (pin "1") (pinfunction "1_1") (pintype "passive"))
    )
    (net (code "42") (name "Net-(U4-USBDM)") (class "Default")
      (node (ref "R13") (pin "2") (pinfunction "2_2") (pintype "passive"))
      (node (ref "U4") (pin "12") (pinfunction "USBDM_12") (pintype "bidirectional"))
    )
    (net (code "43") (name "Net-(U4-USBDP)") (class "Default")
      (node (ref "R14") (pin "2") (pinfunction "2_2") (pintype "passive"))
      (node (ref "U4") (pin "11") (pinfunction "USBDP_11") (pintype "bidirectional"))
    )
    (net (code "44") (name "RESET") (class "Default")
      (node (ref "JP28") (pin "1") (pinfunction "1_1") (pintype "passive"))
      (node (ref "Q2") (pin "3") (pinfunction "C_3") (pintype "passive"))
      (node (ref "R10") (pin "1") (pinfunction "1_1") (pintype "passive"))
      (node (ref "U2") (pin "32") (pinfunction "EXT_RSTB_32") (pintype "bidirectional"))
    )
    (net (code "45") (name "RTS") (class "Default")
      (node (ref "Q2") (pin "2") (pinfunction "E_2") (pintype "passive"))
      (node (ref "R18") (pin "1") (pinfunction "1_1") (pintype "passive"))
      (node (ref "U4") (pin "2") (pinfunction "~{RTS}_2") (pintype "bidirectional"))
    )
    (net (code "46") (name "SD_CLK") (class "Default")
      (node (ref "R9") (pin "1") (pinfunction "1_1") (pintype "passive"))
      (node (ref "U5") (pin "6") (pinfunction "SCK_6") (pintype "bidirectional"))
    )
    (net (code "47") (name "SD_CS0") (class "Default")
      (node (ref "U2") (pin "20") (pinfunction "SPICS0/SD_CMD_20") (pintype "bidirectional"))
      (node (ref "U5") (pin "1") (pinfunction "~{CS}_1") (pintype "bidirectional"))
    )
    (net (code "48") (name "SD_SI") (class "Default")
      (node (ref "U2") (pin "23") (pinfunction "SPID/SD_DATA_1_23") (pintype "bidirectional"))
      (node (ref "U5") (pin "5") (pinfunction "SI(D0)_5") (pintype "bidirectional"))
    )
    (net (code "49") (name "SD_SO") (class "Default")
      (node (ref "U2") (pin "22") (pinfunction "SPIQ/SD_DATA_0_22") (pintype "bidirectional"))
      (node (ref "U5") (pin "2") (pinfunction "SO(D1)_2") (pintype "bidirectional"))
    )
    (net (code "50") (name "SHIELD") (class "Default")
      (node (ref "JP15") (pin "SHIELD1") (pinfunction "SHIELD_SHIELD1") (pintype "bidirectional"))
      (node (ref "JP15") (pin "SHIELD2") (pinfunction "SHIELD_SHIELD2") (pintype "bidirectional"))
      (node (ref "JP15") (pin "SHIELD3") (pinfunction "SHIELD_SHIELD3") (pintype "bidirectional"))
    )
    (net (code "51") (name "U0RXI") (class "Default")
      (node (ref "JP8") (pin "1@2") (pinfunction "1_1@2") (pintype "passive"))
      (node (ref "JP9") (pin "1") (pinfunction "1_1") (pintype "passive"))
      (node (ref "U2") (pin "25") (pinfunction "U0RXD_25") (pintype "bidirectional"))
      (node (ref "U4") (pin "20") (pinfunction "TXD_20") (pintype "bidirectional"))
    )
    (net (code "52") (name "U0TXO") (class "Default")
      (node (ref "JP10") (pin "1@2") (pinfunction "1_1@2") (pintype "passive"))
      (node (ref "JP11") (pin "1") (pinfunction "1_1") (pintype "passive"))
      (node (ref "U2") (pin "26") (pinfunction "U0TXD_26") (pintype "bidirectional"))
      (node (ref "U4") (pin "4") (pinfunction "RXD_4") (pintype "bidirectional"))
    )
    (net (code "53") (name "VCC") (class "Default")
      (node (ref "C1") (pin "1") (pinfunction "1_1") (pintype "passive"))
      (node (ref "C10") (pin "1") (pinfunction "1_1") (pintype "passive"))
      (node (ref "C17") (pin "1") (pinfunction "1_1") (pintype "passive"))
      (node (ref "C18") (pin "1") (pinfunction "1_1") (pintype "passive"))
      (node (ref "C2") (pin "1") (pinfunction "1_1") (pintype "passive"))
      (node (ref "C5") (pin "1") (pinfunction "1_1") (pintype "passive"))
      (node (ref "C9") (pin "1") (pinfunction "1_1") (pintype "passive"))
      (node (ref "D4") (pin "1") (pinfunction "VDD_1") (pintype "power_in"))
      (node (ref "IC1") (pin "8") (pinfunction "V+_8") (pintype "power_in"))
      (node (ref "JP29") (pin "2") (pinfunction "2_2") (pintype "passive"))
      (node (ref "JP30") (pin "2") (pinfunction "2_2") (pintype "passive"))
      (node (ref "JP4") (pin "1@2") (pinfunction "1_1@2") (pintype "passive"))
      (node (ref "JP5") (pin "1") (pinfunction "1_1") (pintype "passive"))
      (node (ref "R10") (pin "2") (pinfunction "2_2") (pintype "passive"))
      (node (ref "R12") (pin "1") (pinfunction "1_1") (pintype "passive"))
      (node (ref "R19") (pin "2") (pinfunction "2_2") (pintype "passive"))
      (node (ref "R8") (pin "2") (pinfunction "2_2") (pintype "passive"))
      (node (ref "SJ3") (pin "2") (pinfunction "2_2") (pintype "passive"))
      (node (ref "SJ4") (pin "2") (pinfunction "2_2") (pintype "passive"))
      (node (ref "U2") (pin "1") (pinfunction "VDDA_1") (pintype "bidirectional"))
      (node (ref "U2") (pin "11") (pinfunction "VDDPST_11") (pintype "bidirectional"))
      (node (ref "U2") (pin "17") (pinfunction "VDDPST_17") (pintype "bidirectional"))
      (node (ref "U2") (pin "29") (pinfunction "VDDD_29") (pintype "bidirectional"))
      (node (ref "U2") (pin "3") (pinfunction "VDD3P3_3") (pintype "bidirectional"))
      (node (ref "U2") (pin "30") (pinfunction "VDDA_30") (pintype "bidirectional"))
      (node (ref "U2") (pin "4") (pinfunction "VDD3P3_4") (pintype "bidirectional"))
      (node (ref "U3") (pin "5") (pinfunction "OUT_5") (pintype "passive"))
      (node (ref "U5") (pin "8") (pinfunction "VCC_8") (pintype "bidirectional"))
      (node (ref "U6") (pin "VDD") (pinfunction "VDD_VDD") (pintype "power_in"))
    )
    (net (code "54") (name "VIN") (class "Default")
      (node (ref "C7") (pin "1") (pinfunction "1_1") (pintype "passive"))
      (node (ref "D2") (pin "C") (pinfunction "C_C") (pintype "passive"))
      (node (ref "JP2") (pin "1@2") (pinfunction "1_1@2") (pintype "passive"))
      (node (ref "JP3") (pin "1") (pinfunction "1_1") (pintype "passive"))
      (node (ref "Q1") (pin "2") (pinfunction "S_2") (pintype "passive"))
      (node (ref "U3") (pin "1") (pinfunction "IN_1") (pintype "input"))
      (node (ref "U3") (pin "3") (pinfunction "EN_3") (pintype "input"))
    )
    (net (code "55") (name "V_BATT") (class "Default")
      (node (ref "C6") (pin "1") (pinfunction "1_1") (pintype "passive"))
      (node (ref "JP1") (pin "2") (pinfunction "2_2") (pintype "passive"))
      (node (ref "Q1") (pin "3") (pinfunction "D_3") (pintype "passive"))
      (node (ref "U1") (pin "3") (pinfunction "VBAT_3") (pintype "power_in"))
    )
    (net (code "56") (name "V_USB") (class "Default")
      (node (ref "C14") (pin "1") (pinfunction "1_1") (pintype "passive"))
      (node (ref "C15") (pin "1") (pinfunction "1_1") (pintype "passive"))
      (node (ref "C19") (pin "1") (pinfunction "1_1") (pintype "passive"))
      (node (ref "D1") (pin "A") (pinfunction "A_A") (pintype "passive"))
      (node (ref "D2") (pin "A") (pinfunction "A_A") (pintype "passive"))
      (node (ref "F1") (pin "2") (pinfunction "2_2") (pintype "bidirectional"))
      (node (ref "Q1") (pin "1") (pinfunction "G_1") (pintype "passive"))
      (node (ref "R7") (pin "2") (pinfunction "2_2") (pintype "passive"))
      (node (ref "U1") (pin "4") (pinfunction "VIN_4") (pintype "power_in"))
      (node (ref "U4") (pin "15") (pinfunction "VCC_15") (pintype "bidirectional"))
    )
    (net (code "57") (name "unconnected-(JP15-PadID)") (class "Default")
      (node (ref "JP15") (pin "ID") (pinfunction "ID_ID") (pintype "bidirectional"))
    )
    (net (code "58") (name "unconnected-(U2-VDD_RTC-Pad5)") (class "Default")
      (node (ref "U2") (pin "5") (pinfunction "VDD_RTC_5") (pintype "bidirectional"))
    )
    (net (code "59") (name "unconnected-(U3-BP-Pad4)") (class "Default")
      (node (ref "U3") (pin "4") (pinfunction "BP_4") (pintype "input"))
    )
    (net (code "60") (name "unconnected-(U4-CBUS0-Pad18)") (class "Default")
      (node (ref "U4") (pin "18") (pinfunction "CBUS0_18") (pintype "bidirectional"))
    )
    (net (code "61") (name "unconnected-(U4-CBUS1-Pad17)") (class "Default")
      (node (ref "U4") (pin "17") (pinfunction "CBUS1_17") (pintype "bidirectional"))
    )
    (net (code "62") (name "unconnected-(U4-CBUS2-Pad10)") (class "Default")
      (node (ref "U4") (pin "10") (pinfunction "CBUS2_10") (pintype "bidirectional"))
    )
    (net (code "63") (name "unconnected-(U4-CBUS3-Pad19)") (class "Default")
      (node (ref "U4") (pin "19") (pinfunction "CBUS3_19") (pintype "bidirectional"))
    )
    (net (code "64") (name "unconnected-(U4-~{CTS}-Pad9)") (class "Default")
      (node (ref "U4") (pin "9") (pinfunction "~{CTS}_9") (pintype "bidirectional"))
    )
    (net (code "65") (name "unconnected-(U4-~{DCD}-Pad8)") (class "Default")
      (node (ref "U4") (pin "8") (pinfunction "~{DCD}_8") (pintype "bidirectional"))
    )
    (net (code "66") (name "unconnected-(U4-~{DSR}-Pad7)") (class "Default")
      (node (ref "U4") (pin "7") (pinfunction "~{DSR}_7") (pintype "bidirectional"))
    )
    (net (code "67") (name "unconnected-(U4-~{RI}-Pad5)") (class "Default")
      (node (ref "U4") (pin "5") (pinfunction "~{RI}_5") (pintype "bidirectional"))
    )
  )
)
